# power.net
KiCad netlist of a schematic drawn in Altium Designer
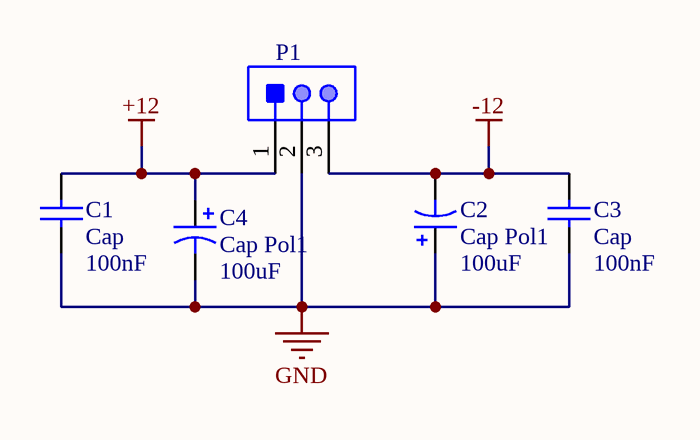
[diagram p0: power.SchDoc]

(export (version "E")
  (design (tool "Eeschema 10.0.6"))
  (components
    (comp (ref "C1")
      (value "Cap")
      (footprint "RAD-0.3")
      (description "Capacitor")
      (fields (field (name "ALTIUM_VALUE") "100nF") (field (name "PUBLISHER") "Altium Limited"))
      (libsource (lib "Miscellaneous Devices") (part "Cap"))
    )
    (comp (ref "C2")
      (value "Cap Pol1")
      (footprint "RB7.6-15")
      (description "Polarized Capacitor (Radial)")
      (fields (field (name "ALTIUM_VALUE") "100uF") (field (name "PUBLISHER") "Altium Limited"))
      (libsource (lib "Miscellaneous Devices") (part "Cap Pol1"))
    )
    (comp (ref "C3")
      (value "Cap")
      (footprint "RAD-0.3")
      (description "Capacitor")
      (fields (field (name "ALTIUM_VALUE") "100nF") (field (name "PUBLISHER") "Altium Limited"))
      (libsource (lib "Miscellaneous Devices") (part "Cap"))
    )
    (comp (ref "C4")
      (value "Cap Pol1")
      (footprint "RB7.6-15")
      (description "Polarized Capacitor (Radial)")
      (fields (field (name "ALTIUM_VALUE") "100uF") (field (name "PUBLISHER") "Altium Limited"))
      (libsource (lib "Miscellaneous Devices") (part "Cap Pol1"))
    )
    (comp (ref "P1")
      (value "171825-3")
      (footprint "TECO-171825-3_V")
      (fields (field (name "MANUFACTURER") "TE Connectivity"))
      (libsource (lib "Altium Content Vault") (part "CN-1P-M-R3"))
    )
  )
  (nets
    (net (code "1") (name "+12") (class "Default")
      (node (ref "C1") (pin "2") (pinfunction "2_2") (pintype "passive"))
      (node (ref "C4") (pin "1") (pinfunction "1_1") (pintype "passive"))
      (node (ref "P1") (pin "1") (pinfunction "1_1") (pintype "passive"))
    )
    (net (code "2") (name "-12") (class "Default")
      (node (ref "C2") (pin "2") (pinfunction "2_2") (pintype "passive"))
      (node (ref "C3") (pin "2") (pinfunction "2_2") (pintype "passive"))
      (node (ref "P1") (pin "3") (pinfunction "3_3") (pintype "passive"))
    )
    (net (code "3") (name "GND") (class "Default")
      (node (ref "C1") (pin "1") (pinfunction "1_1") (pintype "passive"))
      (node (ref "C2") (pin "1") (pinfunction "1_1") (pintype "passive"))
      (node (ref "C3") (pin "1") (pinfunction "1_1") (pintype "passive"))
      (node (ref "C4") (pin "2") (pinfunction "2_2") (pintype "passive"))
      (node (ref "P1") (pin "2") (pinfunction "2_2") (pintype "passive"))
    )
  )
)
